# pH_sensor.net
KiCad netlist of a schematic drawn in Altium Designer
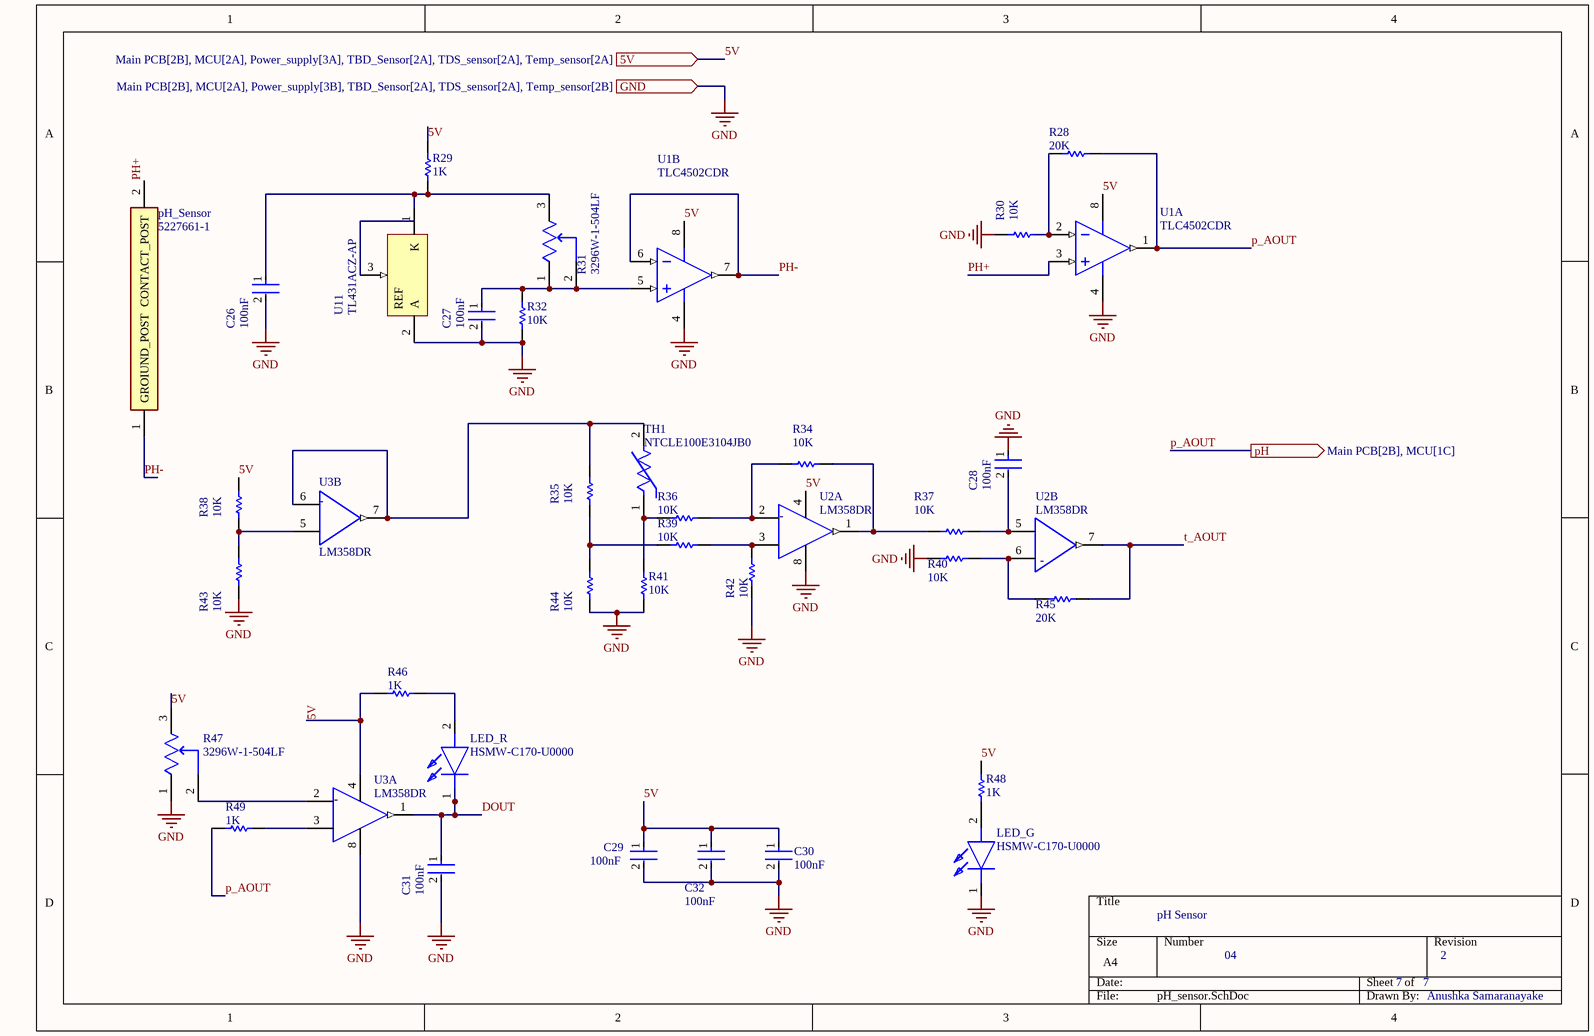
[diagram p0: pH_sensor.SchDoc]

(export (version "E")
  (design (tool "Eeschema 10.0.6"))
  (components
    (comp (ref "C26")
      (value "100nF")
      (footprint "FP-CL31-IPC_B")
      (description "Cap Ceramic 100nF 50V X7R ±10% SMD 1206 +125°C Embossed T/R")
      (fields (field (name "VOLTAGE") "50V") (field (name "TOLERANCE") "10%"))
      (libsource (lib "Altium Content Vault") (part "b4654b650e69147ec39a6b967a45e02"))
    )
    (comp (ref "C27")
      (value "100nF")
      (footprint "FP-CL31-IPC_B")
      (description "Cap Ceramic 100nF 50V X7R ±10% SMD 1206 +125°C Embossed T/R")
      (fields (field (name "VOLTAGE") "50V") (field (name "TOLERANCE") "10%"))
      (libsource (lib "Altium Content Vault") (part "b4654b650e69147ec39a6b967a45e02"))
    )
    (comp (ref "C28")
      (value "100nF")
      (footprint "FP-CL31-IPC_B")
      (description "Cap Ceramic 100nF 50V X7R ±10% SMD 1206 +125°C Embossed T/R")
      (fields (field (name "VOLTAGE") "50V") (field (name "TOLERANCE") "10%"))
      (libsource (lib "Altium Content Vault") (part "b4654b650e69147ec39a6b967a45e02"))
    )
    (comp (ref "C29")
      (value "100nF")
      (footprint "FP-CL31-IPC_B")
      (description "Cap Ceramic 100nF 50V X7R ±10% SMD 1206 +125°C Embossed T/R")
      (fields (field (name "VOLTAGE") "50V") (field (name "TOLERANCE") "10%"))
      (libsource (lib "Altium Content Vault") (part "b4654b650e69147ec39a6b967a45e02"))
    )
    (comp (ref "C30")
      (value "100nF")
      (footprint "FP-CL31-IPC_B")
      (description "Cap Ceramic 100nF 50V X7R ±10% SMD 1206 +125°C Embossed T/R")
      (fields (field (name "VOLTAGE") "50V") (field (name "TOLERANCE") "10%"))
      (libsource (lib "Altium Content Vault") (part "b4654b650e69147ec39a6b967a45e02"))
    )
    (comp (ref "C31")
      (value "100nF")
      (footprint "FP-CL31-IPC_B")
      (description "Cap Ceramic 100nF 50V X7R ±10% SMD 1206 +125°C Embossed T/R")
      (fields (field (name "VOLTAGE") "50V") (field (name "TOLERANCE") "10%"))
      (libsource (lib "Altium Content Vault") (part "b4654b650e69147ec39a6b967a45e02"))
    )
    (comp (ref "C32")
      (value "100nF")
      (footprint "FP-CL31-IPC_B")
      (description "Cap Ceramic 100nF 50V X7R ±10% SMD 1206 +125°C Embossed T/R")
      (fields (field (name "VOLTAGE") "50V") (field (name "TOLERANCE") "10%"))
      (libsource (lib "Altium Content Vault") (part "b4654b650e69147ec39a6b967a45e02"))
    )
    (comp (ref "LED_G")
      (value "HSMW-C170-U0000")
      (footprint "SamacSys:LEDC2012X90N")
      (description "LED")
      (fields (field (name "MOUSER PART NUMBER") "630-HSMW-C170-U0000"))
      (libsource (lib "*") (part "HSMW-C170-U0000"))
    )
    (comp (ref "LED_R")
      (value "HSMW-C170-U0000")
      (footprint "SamacSys:LEDC2012X90N")
      (description "LED")
      (fields (field (name "MOUSER PART NUMBER") "630-HSMW-C170-U0000"))
      (libsource (lib "*") (part "HSMW-C170-U0000"))
    )
    (comp (ref "pH_Sensor")
      (value "5227661-1")
      (footprint "SamacSys:5227161-1")
      (description "Connector")
      (fields (field (name "MOUSER PART NUMBER") "571-5227661-1"))
      (libsource (lib "*") (part "5227661-1"))
    )
    (comp (ref "R28")
      (value "20K")
      (footprint "RESC3216X70X50LL20T25")
      (fields (field (name "MANUFACTURER") "Panasonic") (field (name "PART NUMBER") "ERA8AEB103V"))
      (libsource (lib "Altium Content Vault") (part "RES"))
    )
    (comp (ref "R29")
      (value "1K")
      (footprint "RESC3216X70X50ML20T25")
      (fields (field (name "PART NUMBER") "ERA8AEB102V") (field (name "MANUFACTURER") "Panasonic"))
      (libsource (lib "Altium Content Vault") (part "RES"))
    )
    (comp (ref "R30")
      (value "10K")
      (footprint "RESC3216X70X50LL20T25")
      (fields (field (name "MANUFACTURER") "Panasonic") (field (name "PART NUMBER") "ERA8AEB103V"))
      (libsource (lib "Altium Content Vault") (part "RES"))
    )
    (comp (ref "R31")
      (value "3296W-1-504LF")
      (footprint "FP-3296W-MFG")
      (description "TRIMMER 500K OHM 0.5W PC PIN TOP")
      (fields
        (field (name "MANUFACTURER") "Bourns")
        (field (name "OCTOPART") "https://octopart.com/3296w-1-504lf-bourns-143884")
      )
      (libsource (lib "Altium Content Vault") (part "8d460c8a6f7ec10b1759d1b9c49aa93"))
    )
    (comp (ref "R32")
      (value "10K")
      (footprint "RESC3216X70X50LL20T25")
      (fields (field (name "MANUFACTURER") "Panasonic") (field (name "PART NUMBER") "ERA8AEB103V"))
      (libsource (lib "Altium Content Vault") (part "RES"))
    )
    (comp (ref "R34")
      (value "10K")
      (footprint "RESC3216X70X50LL20T25")
      (fields (field (name "MANUFACTURER") "Panasonic") (field (name "PART NUMBER") "ERA8AEB103V"))
      (libsource (lib "Altium Content Vault") (part "RES"))
    )
    (comp (ref "R35")
      (value "10K")
      (footprint "RESC3216X70X50LL20T25")
      (fields (field (name "MANUFACTURER") "Panasonic") (field (name "PART NUMBER") "ERA8AEB103V"))
      (libsource (lib "Altium Content Vault") (part "RES"))
    )
    (comp (ref "R36")
      (value "10K")
      (footprint "RESC3216X70X50LL20T25")
      (fields (field (name "MANUFACTURER") "Panasonic") (field (name "PART NUMBER") "ERA8AEB103V"))
      (libsource (lib "Altium Content Vault") (part "RES"))
    )
    (comp (ref "R37")
      (value "10K")
      (footprint "RESC3216X70X50LL20T25")
      (fields (field (name "MANUFACTURER") "Panasonic") (field (name "PART NUMBER") "ERA8AEB103V"))
      (libsource (lib "Altium Content Vault") (part "RES"))
    )
    (comp (ref "R38")
      (value "10K")
      (footprint "RESC3216X70X50LL20T25")
      (fields (field (name "MANUFACTURER") "Panasonic") (field (name "PART NUMBER") "ERA8AEB103V"))
      (libsource (lib "Altium Content Vault") (part "RES"))
    )
    (comp (ref "R39")
      (value "10K")
      (footprint "RESC3216X70X50LL20T25")
      (fields (field (name "MANUFACTURER") "Panasonic") (field (name "PART NUMBER") "ERA8AEB103V"))
      (libsource (lib "Altium Content Vault") (part "RES"))
    )
    (comp (ref "R40")
      (value "10K")
      (footprint "RESC3216X70X50LL20T25")
      (fields (field (name "MANUFACTURER") "Panasonic") (field (name "PART NUMBER") "ERA8AEB103V"))
      (libsource (lib "Altium Content Vault") (part "RES"))
    )
    (comp (ref "R41")
      (value "10K")
      (footprint "RESC3216X70X50LL20T25")
      (fields (field (name "MANUFACTURER") "Panasonic") (field (name "PART NUMBER") "ERA8AEB103V"))
      (libsource (lib "Altium Content Vault") (part "RES"))
    )
    (comp (ref "R42")
      (value "10K")
      (footprint "RESC3216X70X50LL20T25")
      (fields (field (name "MANUFACTURER") "Panasonic") (field (name "PART NUMBER") "ERA8AEB103V"))
      (libsource (lib "Altium Content Vault") (part "RES"))
    )
    (comp (ref "R43")
      (value "10K")
      (footprint "RESC3216X70X50LL20T25")
      (fields (field (name "MANUFACTURER") "Panasonic") (field (name "PART NUMBER") "ERA8AEB103V"))
      (libsource (lib "Altium Content Vault") (part "RES"))
    )
    (comp (ref "R44")
      (value "10K")
      (footprint "RESC3216X70X50LL20T25")
      (fields (field (name "MANUFACTURER") "Panasonic") (field (name "PART NUMBER") "ERA8AEB103V"))
      (libsource (lib "Altium Content Vault") (part "RES"))
    )
    (comp (ref "R45")
      (value "20K")
      (footprint "RESC3216X70X50LL20T25")
      (fields (field (name "MANUFACTURER") "Panasonic") (field (name "PART NUMBER") "ERA8AEB103V"))
      (libsource (lib "Altium Content Vault") (part "RES"))
    )
    (comp (ref "R46")
      (value "1K")
      (footprint "RESC3216X70X50ML20T25")
      (fields (field (name "PART NUMBER") "ERA8AEB102V") (field (name "MANUFACTURER") "Panasonic"))
      (libsource (lib "Altium Content Vault") (part "RES"))
    )
    (comp (ref "R47")
      (value "3296W-1-504LF")
      (footprint "FP-3296W-MFG")
      (description "TRIMMER 500K OHM 0.5W PC PIN TOP")
      (fields
        (field (name "MANUFACTURER") "Bourns")
        (field (name "OCTOPART") "https://octopart.com/3296w-1-504lf-bourns-143884")
      )
      (libsource (lib "Altium Content Vault") (part "8d460c8a6f7ec10b1759d1b9c49aa93"))
    )
    (comp (ref "R48")
      (value "1K")
      (footprint "RESC3216X70X50ML20T25")
      (fields (field (name "PART NUMBER") "ERA8AEB102V") (field (name "MANUFACTURER") "Panasonic"))
      (libsource (lib "Altium Content Vault") (part "RES"))
    )
    (comp (ref "R49")
      (value "1K")
      (footprint "RESC3216X70X50ML20T25")
      (fields (field (name "PART NUMBER") "ERA8AEB102V") (field (name "MANUFACTURER") "Panasonic"))
      (libsource (lib "Altium Content Vault") (part "RES"))
    )
    (comp (ref "TH1")
      (value "NTCLE100E3104JB0")
      (footprint "FP-NTCLE100E3104JB0-MFG")
      (description "NTC THERMISTOR 100K OHM 5% BEAD")
      (fields (field (name "TOLERANCE") "5%"))
      (libsource (lib "Altium Content Vault") (part "3b148a6ebabc5fb4d708a66c052d352"))
    )
    (comp (ref "U1")
      (value "TLC4502CDR")
      (footprint "D0008A_M")
      (fields (field (name "MANUFACTURER") "Texas Instruments"))
      (libsource (lib "Altium Content Vault") (part "TI-TLV_C2XX2_TLC4502-8"))
    )
    (comp (ref "U2")
      (value "LM358DR")
      (footprint "FP-D0008A-MFG")
      (description "IC OPAMP GP 2 CIRCUIT 8SOIC")
      (libsource (lib "Altium Content Vault") (part "0afdfe5f461d2cdd85604ff8654be97"))
    )
    (comp (ref "U3")
      (value "LM358DR")
      (footprint "FP-D0008A-MFG")
      (description "IC OPAMP GP 2 CIRCUIT 8SOIC")
      (libsource (lib "Altium Content Vault") (part "0afdfe5f461d2cdd85604ff8654be97"))
    )
    (comp (ref "U11")
      (value "TL431ACZ-AP")
      (footprint "TO-92")
      (description "Programmable Voltage Reference, 2.5 to 36V, 3-Pin TO-92, Ammopak")
      (libsource (lib "Altium Content Vault") (part "PM-REF-431-SIL3"))
    )
  )
  (nets
    (net (code "1") (name "/5V") (class "Default")
      (node (ref "C29") (pin "1") (pinfunction "1_1") (pintype "passive"))
      (node (ref "C30") (pin "1") (pinfunction "1_1") (pintype "passive"))
      (node (ref "C32") (pin "1") (pinfunction "1_1") (pintype "passive"))
      (node (ref "R29") (pin "1") (pinfunction "1_1") (pintype "passive"))
      (node (ref "R38") (pin "2") (pinfunction "2_2") (pintype "passive"))
      (node (ref "R46") (pin "1") (pinfunction "1_1") (pintype "passive"))
      (node (ref "R47") (pin "3") (pinfunction "CW_3") (pintype "passive"))
      (node (ref "R48") (pin "1") (pinfunction "1_1") (pintype "passive"))
      (node (ref "U1") (pin "8") (pinfunction "VDD+_8") (pintype "passive"))
      (node (ref "U2") (pin "4") (pinfunction "V-_4") (pintype "power_in"))
      (node (ref "U3") (pin "4") (pinfunction "V-_4") (pintype "power_in"))
    )
    (net (code "2") (name "/DOUT") (class "Default")
      (node (ref "C31") (pin "1") (pinfunction "1_1") (pintype "passive"))
      (node (ref "LED_R") (pin "1") (pinfunction "K_1") (pintype "passive"))
      (node (ref "U3") (pin "1") (pinfunction "1OUT_1") (pintype "output"))
    )
    (net (code "3") (name "/PH+") (class "Default")
      (node (ref "U1") (pin "3") (pinfunction "IN1+_3") (pintype "input"))
      (node (ref "pH_Sensor") (pin "2") (pinfunction "CONTACT_POST_2") (pintype "passive"))
    )
    (net (code "4") (name "/PH-") (class "Default")
      (node (ref "U1") (pin "6") (pinfunction "IN2-_6") (pintype "input"))
      (node (ref "U1") (pin "7") (pinfunction "OUT2_7") (pintype "output"))
      (node (ref "pH_Sensor") (pin "1") (pinfunction "GROIUND_POST_1") (pintype "passive"))
    )
    (net (code "5") (name "/p_AOUT") (class "Default")
      (node (ref "R28") (pin "2") (pinfunction "2_2") (pintype "passive"))
      (node (ref "R49") (pin "1") (pinfunction "1_1") (pintype "passive"))
      (node (ref "U1") (pin "1") (pinfunction "OUT1_1") (pintype "output"))
    )
    (net (code "6") (name "/t_AOUT") (class "Default")
      (node (ref "R45") (pin "2") (pinfunction "2_2") (pintype "passive"))
      (node (ref "U2") (pin "7") (pinfunction "2OUT_7") (pintype "output"))
    )
    (net (code "7") (name "GND") (class "Default")
      (node (ref "C26") (pin "2") (pinfunction "2_2") (pintype "passive"))
      (node (ref "C27") (pin "2") (pinfunction "2_2") (pintype "passive"))
      (node (ref "C28") (pin "1") (pinfunction "1_1") (pintype "passive"))
      (node (ref "C29") (pin "2") (pinfunction "2_2") (pintype "passive"))
      (node (ref "C30") (pin "2") (pinfunction "2_2") (pintype "passive"))
      (node (ref "C31") (pin "2") (pinfunction "2_2") (pintype "passive"))
      (node (ref "C32") (pin "2") (pinfunction "2_2") (pintype "passive"))
      (node (ref "LED_G") (pin "1") (pinfunction "K_1") (pintype "passive"))
      (node (ref "R30") (pin "1") (pinfunction "1_1") (pintype "passive"))
      (node (ref "R32") (pin "1") (pinfunction "1_1") (pintype "passive"))
      (node (ref "R40") (pin "1") (pinfunction "1_1") (pintype "passive"))
      (node (ref "R41") (pin "1") (pinfunction "1_1") (pintype "passive"))
      (node (ref "R42") (pin "1") (pinfunction "1_1") (pintype "passive"))
      (node (ref "R43") (pin "1") (pinfunction "1_1") (pintype "passive"))
      (node (ref "R44") (pin "1") (pinfunction "1_1") (pintype "passive"))
      (node (ref "R47") (pin "1") (pinfunction "CCW_1") (pintype "passive"))
      (node (ref "U1") (pin "4") (pinfunction "VDD-/GND_4") (pintype "passive"))
      (node (ref "U11") (pin "2") (pinfunction "A_2") (pintype "passive"))
      (node (ref "U2") (pin "8") (pinfunction "V+_8") (pintype "power_in"))
      (node (ref "U3") (pin "8") (pinfunction "V+_8") (pintype "power_in"))
    )
    (net (code "8") (name "Net-(LED_G-A)") (class "Default")
      (node (ref "LED_G") (pin "2") (pinfunction "A_2") (pintype "passive"))
      (node (ref "R48") (pin "2") (pinfunction "2_2") (pintype "passive"))
    )
    (net (code "9") (name "Net-(LED_R-A)") (class "Default")
      (node (ref "LED_R") (pin "2") (pinfunction "A_2") (pintype "passive"))
      (node (ref "R46") (pin "2") (pinfunction "2_2") (pintype "passive"))
    )
    (net (code "10") (name "Net-(R31-CCW)") (class "Default")
      (node (ref "C27") (pin "1") (pinfunction "1_1") (pintype "passive"))
      (node (ref "R31") (pin "1") (pinfunction "CCW_1") (pintype "passive"))
      (node (ref "R31") (pin "2") (pinfunction "WIPER_2") (pintype "passive"))
      (node (ref "R32") (pin "2") (pinfunction "2_2") (pintype "passive"))
      (node (ref "U1") (pin "5") (pinfunction "IN2+_5") (pintype "input"))
    )
    (net (code "11") (name "Net-(R31-CW)") (class "Default")
      (node (ref "C26") (pin "1") (pinfunction "1_1") (pintype "passive"))
      (node (ref "R29") (pin "2") (pinfunction "2_2") (pintype "passive"))
      (node (ref "R31") (pin "3") (pinfunction "CW_3") (pintype "passive"))
      (node (ref "U11") (pin "1") (pinfunction "K_1") (pintype "passive"))
    )
    (net (code "12") (name "Net-(R35-Pad1)") (class "Default")
      (node (ref "R35") (pin "1") (pinfunction "1_1") (pintype "passive"))
      (node (ref "R39") (pin "1") (pinfunction "1_1") (pintype "passive"))
      (node (ref "R44") (pin "2") (pinfunction "2_2") (pintype "passive"))
    )
    (net (code "13") (name "Net-(R36-Pad1)") (class "Default")
      (node (ref "R36") (pin "1") (pinfunction "1_1") (pintype "passive"))
      (node (ref "R41") (pin "2") (pinfunction "2_2") (pintype "passive"))
      (node (ref "TH1") (pin "1") (pinfunction "1_1") (pintype "passive"))
    )
    (net (code "14") (name "Net-(R47-WIPER)") (class "Default")
      (node (ref "R47") (pin "2") (pinfunction "WIPER_2") (pintype "passive"))
      (node (ref "U3") (pin "2") (pinfunction "IN1-_2") (pintype "tri_state"))
    )
    (net (code "15") (name "Net-(U1A-IN1-)") (class "Default")
      (node (ref "R28") (pin "1") (pinfunction "1_1") (pintype "passive"))
      (node (ref "R30") (pin "2") (pinfunction "2_2") (pintype "passive"))
      (node (ref "U1") (pin "2") (pinfunction "IN1-_2") (pintype "input"))
    )
    (net (code "16") (name "Net-(U2A-1OUT)") (class "Default")
      (node (ref "R34") (pin "2") (pinfunction "2_2") (pintype "passive"))
      (node (ref "R37") (pin "1") (pinfunction "1_1") (pintype "passive"))
      (node (ref "U2") (pin "1") (pinfunction "1OUT_1") (pintype "output"))
    )
    (net (code "17") (name "Net-(U2A-IN1+)") (class "Default")
      (node (ref "R39") (pin "2") (pinfunction "2_2") (pintype "passive"))
      (node (ref "R42") (pin "2") (pinfunction "2_2") (pintype "passive"))
      (node (ref "U2") (pin "3") (pinfunction "IN1+_3") (pintype "tri_state"))
    )
    (net (code "18") (name "Net-(U2A-IN1-)") (class "Default")
      (node (ref "R34") (pin "1") (pinfunction "1_1") (pintype "passive"))
      (node (ref "R36") (pin "2") (pinfunction "2_2") (pintype "passive"))
      (node (ref "U2") (pin "2") (pinfunction "IN1-_2") (pintype "tri_state"))
    )
    (net (code "19") (name "Net-(U2B-IN2+)") (class "Default")
      (node (ref "C28") (pin "2") (pinfunction "2_2") (pintype "passive"))
      (node (ref "R37") (pin "2") (pinfunction "2_2") (pintype "passive"))
      (node (ref "U2") (pin "5") (pinfunction "IN2+_5") (pintype "tri_state"))
    )
    (net (code "20") (name "Net-(U2B-IN2-)") (class "Default")
      (node (ref "R40") (pin "2") (pinfunction "2_2") (pintype "passive"))
      (node (ref "R45") (pin "1") (pinfunction "1_1") (pintype "passive"))
      (node (ref "U2") (pin "6") (pinfunction "IN2-_6") (pintype "tri_state"))
    )
    (net (code "21") (name "Net-(U3A-IN1+)") (class "Default")
      (node (ref "R49") (pin "2") (pinfunction "2_2") (pintype "passive"))
      (node (ref "U3") (pin "3") (pinfunction "IN1+_3") (pintype "tri_state"))
    )
    (net (code "22") (name "Net-(U3B-2OUT)") (class "Default")
      (node (ref "R35") (pin "2") (pinfunction "2_2") (pintype "passive"))
      (node (ref "TH1") (pin "2") (pinfunction "2_2") (pintype "passive"))
      (node (ref "U3") (pin "6") (pinfunction "IN2-_6") (pintype "tri_state"))
      (node (ref "U3") (pin "7") (pinfunction "2OUT_7") (pintype "output"))
    )
    (net (code "23") (name "Net-(U3B-IN2+)") (class "Default")
      (node (ref "R38") (pin "1") (pinfunction "1_1") (pintype "passive"))
      (node (ref "R43") (pin "2") (pinfunction "2_2") (pintype "passive"))
      (node (ref "U3") (pin "5") (pinfunction "IN2+_5") (pintype "tri_state"))
    )
    (net (code "24") (name "unconnected-(U11-REF-Pad3)") (class "Default")
      (node (ref "U11") (pin "3") (pinfunction "REF_3") (pintype "input"))
    )
  )
)
